# Power.net
KiCad netlist of a schematic drawn in Altium Designer
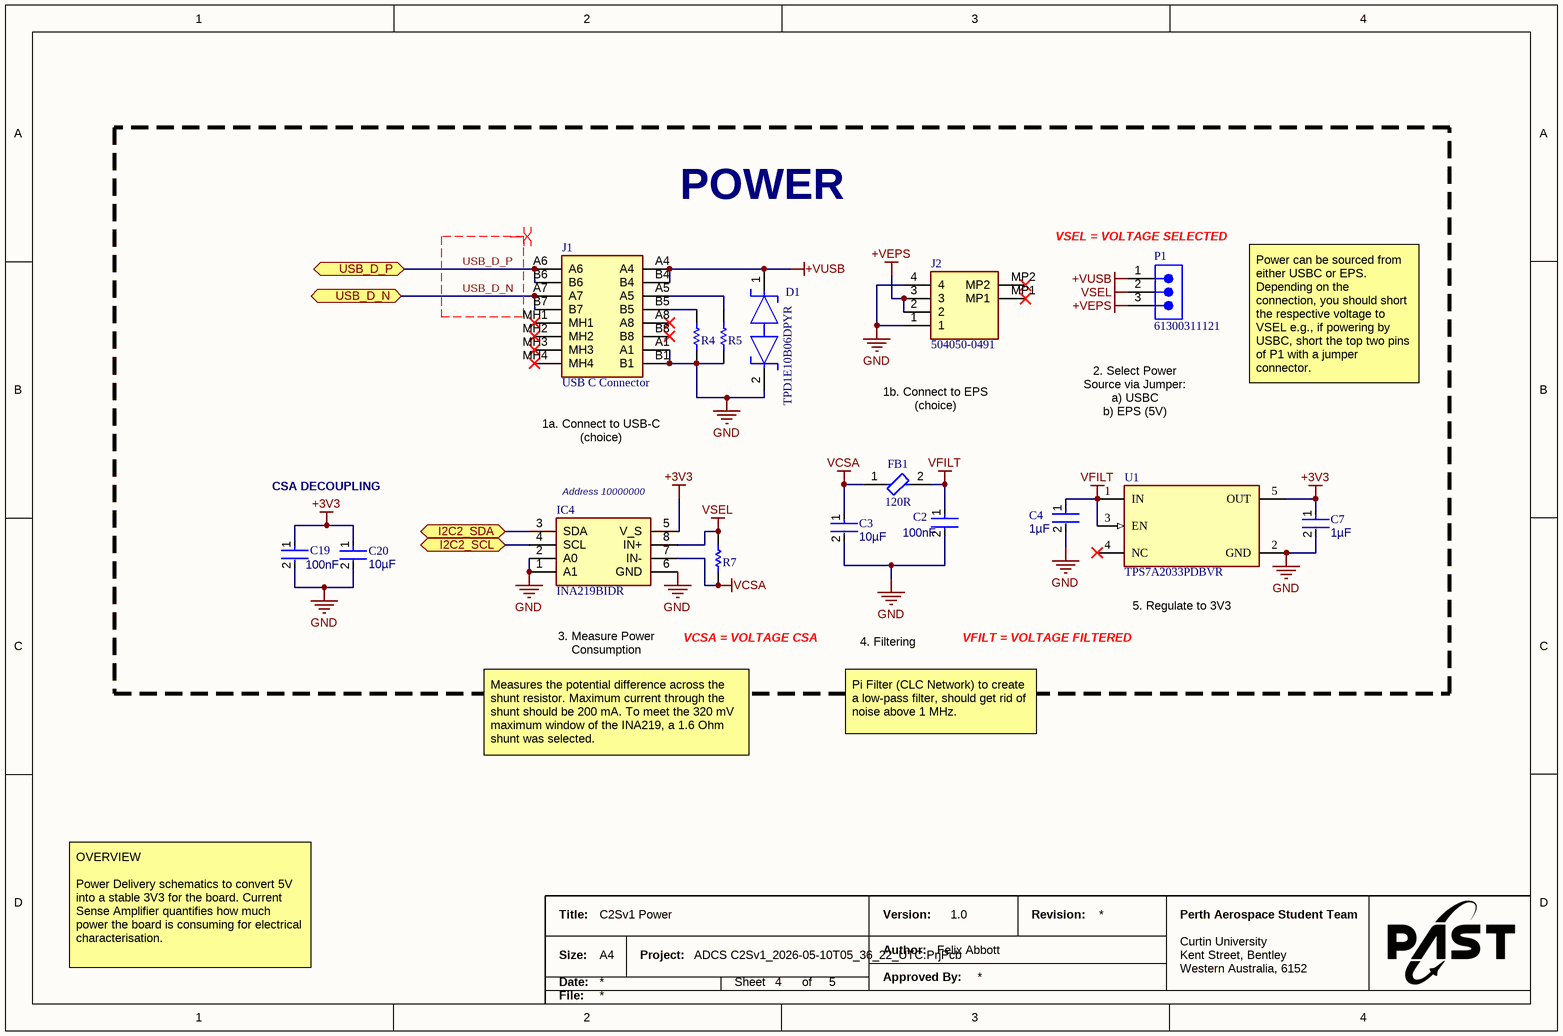
[diagram p0: Power.SchDoc]

(export (version "E")
  (design (tool "Eeschema 10.0.6"))
  (components
    (comp (ref "C2")
      (value "100nF")
      (footprint "FP-GCM188-0_1-IPC_B")
      (description "Cap Ceramic 0.1uF 50V X8L 20% Pad SMD 0603 150C Automotive T/R")
      (fields
        (field (name "TOLERANCE") "20%")
        (field (name "Comment") "GCM188L81H104MA57D")
        (field (name "ADDED BY") "Felix")
      )
      (libsource (lib "Perth Aerospace Student Team") (part "02cd4be3c70576c341d710602a673aa"))
    )
    (comp (ref "C3")
      (value "10µF")
      (footprint "FP-GCM188-0_2-IPC_B")
      (description "6.3V 10uF X7T ±20% 0603 Multilayer Ceramic Capacitors MLCC - SMD/SMT ROHS")
      (fields
        (field (name "TOLERANCE") "20%")
        (field (name "Comment") "GCM188D70J106ME36D")
        (field (name "ADDED BY") "Felix")
      )
      (libsource (lib "Perth Aerospace Student Team") (part "11868f565c42a9108669ba33697ecf6"))
    )
    (comp (ref "C4")
      (value "1µF")
      (footprint "FP-GCM188-0_1-IPC_B")
      (description "16V 1uF X7R ±10% 0603 Multilayer Ceramic Capacitors MLCC - SMD/SMT ROHS")
      (fields
        (field (name "TOLERANCE") "10%")
        (field (name "Comment") "GCM188R71C105KA64J")
        (field (name "ADDED BY") "Felix")
      )
      (libsource (lib "Perth Aerospace Student Team") (part "02cd4be3c70576c341d710602a673aa"))
    )
    (comp (ref "C7")
      (value "1µF")
      (footprint "FP-GCM188-0_1-IPC_B")
      (description "16V 1uF X7R ±10% 0603 Multilayer Ceramic Capacitors MLCC - SMD/SMT ROHS")
      (fields
        (field (name "TOLERANCE") "10%")
        (field (name "Comment") "GCM188R71C105KA64J")
        (field (name "ADDED BY") "Felix")
      )
      (libsource (lib "Perth Aerospace Student Team") (part "02cd4be3c70576c341d710602a673aa"))
    )
    (comp (ref "C19")
      (value "100nF")
      (footprint "FP-GCM188-0_1-IPC_B")
      (description "Cap Ceramic 0.1uF 50V X8L 20% Pad SMD 0603 150C Automotive T/R")
      (fields
        (field (name "TOLERANCE") "20%")
        (field (name "Comment") "GCM188L81H104MA57D")
        (field (name "ADDED BY") "Felix")
      )
      (libsource (lib "Perth Aerospace Student Team") (part "02cd4be3c70576c341d710602a673aa"))
    )
    (comp (ref "C20")
      (value "10µF")
      (footprint "FP-GCM188-0_2-IPC_B")
      (description "6.3V 10uF X7T ±20% 0603 Multilayer Ceramic Capacitors MLCC - SMD/SMT ROHS")
      (fields (field (name "TOLERANCE") "20%") (field (name "ADDED BY") "Felix"))
      (libsource (lib "Perth Aerospace Student Team") (part "11868f565c42a9108669ba33697ecf6"))
    )
    (comp (ref "D1")
      (value "TPD1E10B06DPYR")
      (footprint "FP-DPY0002A-MFG")
      (description "TVS DIODE 5.5V 14V 2X1SON")
      (libsource (lib "Altium Content Vault") (part "208e19b57522434895fa003e5d5b197"))
    )
    (comp (ref "FB1")
      (value "120R")
      (footprint "FP-BLM18-0_15-t0_6-d1_2-IPC_B")
      (description "Chip Ferrite Bead Array, 0603, 120Ω @ 100MHz, 25%, 0.03Ω, 3A")
      (libsource (lib "Altium Content Vault") (part "5f30dd21d616792df468990f7003faa"))
    )
    (comp (ref "IC4")
      (value "INA219BIDR")
      (footprint "SOIC127P600X175-8N")
      (description "Integrated Circuit")
      (fields (field (name "MOUSER PART NUMBER") "595-INA219BIDR") (field (name "AUTHOR") "Damon Stewart"))
      (libsource (lib "Perth Aerospace Student Team") (part "INA219BIDR"))
    )
    (comp (ref "J1")
      (value "USB C Connector")
      (footprint "UJ20CHGMSMT2P16TR")
      (description "UJ20-C-H-G-MSMT-2-P16-TR Connector")
      (fields
        (field (name "MOUSER PART NUMBER") "179-UJ20CHGMSMT2P16T")
        (field (name "MANUFACTURER_PART_NUMBER") "UJ20-C-H-G-MSMT-2-P16-TR")
        (field (name "AUTHOR") "Raphael Ho")
      )
      (libsource (lib "Perth Aerospace Student Team") (part "UJ20-C-H-G-MSMT-2-P16-TR"))
    )
    (comp (ref "J2")
      (value "504050-0491")
      (footprint "5040500491")
      (description "Connector")
      (fields (field (name "MOUSER PART NUMBER") "538-504050-0491"))
      (libsource (lib "Perth Aerospace Student Team") (part "504050-0491"))
    )
    (comp (ref "P1")
      (value "61300311121")
      (footprint "61300311121")
      (description "WR-PHD Pin Header, THT, Vertical, pitch 2.54mm, 1 Row, 3P")
      (fields (field (name "MANUFACTURER") "Wurth Elektronik"))
      (libsource (lib "Perth Aerospace Student Team") (part "62000311121"))
    )
    (comp (ref "R4")
      (value "5.1k")
      (footprint "RESC1608X55N")
      (description "AC0603FR-7W5K1L Resistor")
      (fields
        (field (name "MANUFACTURER_PART_NUMBER") "AC0603FR-7W5K1L")
        (field (name "AUTHOR") "Raphael Ho")
      )
      (libsource (lib "Perth Aerospace Student Team") (part "CRCW0603300RFKEAHP"))
    )
    (comp (ref "R5")
      (value "5.1k")
      (footprint "RESC1608X55N")
      (description "AC0603FR-7W5K1L Resistor")
      (fields
        (field (name "MANUFACTURER_PART_NUMBER") "AC0603FR-7W5K1L")
        (field (name "AUTHOR") "Raphael Ho")
      )
      (libsource (lib "Perth Aerospace Student Team") (part "CRCW0603300RFKEAHP"))
    )
    (comp (ref "R7")
      (value "ERJ-6DQF1R6V")
      (footprint "ERJ6_B_BW_R_LW_CW_D")
      (description "SMD Current Sense Resistor")
      (fields (field (name "MOUSER PART NUMBER") "667-ERJ-6DQF1R6V") (field (name "ADDED BY") "Felix"))
      (libsource (lib "Perth Aerospace Student Team") (part "ERJ-6DQF1R6V"))
    )
    (comp (ref "U1")
      (value "TPS7A2033PDBVR")
      (footprint "FP-DBV0005A-IPC_B")
      (description "300mA ultra-low-noise low-IQ low-dropout (LDO) linear regulator with high PSRR 5-SOT-23 -40 to 125")
      (fields (field (name "ADDED BY") "Felix Abbott"))
      (libsource (lib "Perth Aerospace Student Team") (part "76aa7ad0ceb1012e0d85aeafc53095f"))
    )
  )
  (nets
    (net (code "1") (name "+3V3") (class "Default")
      (node (ref "C19") (pin "1") (pinfunction "1_1") (pintype "passive"))
      (node (ref "C20") (pin "1") (pinfunction "1_1") (pintype "passive"))
      (node (ref "C7") (pin "1") (pinfunction "1_1") (pintype "passive"))
      (node (ref "IC4") (pin "5") (pinfunction "V_S_5") (pintype "passive"))
      (node (ref "U1") (pin "5") (pinfunction "OUT_5") (pintype "passive"))
    )
    (net (code "2") (name "+VEPS") (class "Default")
      (node (ref "J2") (pin "2") (pinfunction "2_2") (pintype "passive"))
      (node (ref "J2") (pin "3") (pinfunction "3_3") (pintype "passive"))
      (node (ref "P1") (pin "3") (pinfunction "3_3") (pintype "passive"))
    )
    (net (code "3") (name "+VUSB") (class "Default")
      (node (ref "D1") (pin "1") (pinfunction "1_1") (pintype "passive"))
      (node (ref "J1") (pin "A4") (pinfunction "A4_A4") (pintype "passive"))
      (node (ref "J1") (pin "B4") (pinfunction "B4_B4") (pintype "passive"))
      (node (ref "P1") (pin "1") (pinfunction "1_1") (pintype "passive"))
    )
    (net (code "4") (name "/I2C2_SCL") (class "Default")
      (node (ref "IC4") (pin "4") (pinfunction "SCL_4") (pintype "passive"))
    )
    (net (code "5") (name "/I2C2_SDA") (class "Default")
      (node (ref "IC4") (pin "3") (pinfunction "SDA_3") (pintype "passive"))
    )
    (net (code "6") (name "/USB_D_N") (class "Default")
      (node (ref "J1") (pin "A7") (pinfunction "A7_A7") (pintype "passive"))
      (node (ref "J1") (pin "B7") (pinfunction "B7_B7") (pintype "passive"))
    )
    (net (code "7") (name "/USB_D_P") (class "Default")
      (node (ref "J1") (pin "A6") (pinfunction "A6_A6") (pintype "passive"))
      (node (ref "J1") (pin "B6") (pinfunction "B6_B6") (pintype "passive"))
    )
    (net (code "8") (name "GND") (class "Default")
      (node (ref "C19") (pin "2") (pinfunction "2_2") (pintype "passive"))
      (node (ref "C2") (pin "2") (pinfunction "2_2") (pintype "passive"))
      (node (ref "C20") (pin "2") (pinfunction "2_2") (pintype "passive"))
      (node (ref "C3") (pin "2") (pinfunction "2_2") (pintype "passive"))
      (node (ref "C4") (pin "2") (pinfunction "2_2") (pintype "passive"))
      (node (ref "C7") (pin "2") (pinfunction "2_2") (pintype "passive"))
      (node (ref "D1") (pin "2") (pinfunction "2_2") (pintype "passive"))
      (node (ref "IC4") (pin "1") (pinfunction "A1_1") (pintype "passive"))
      (node (ref "IC4") (pin "2") (pinfunction "A0_2") (pintype "passive"))
      (node (ref "IC4") (pin "6") (pinfunction "GND_6") (pintype "passive"))
      (node (ref "J1") (pin "A1") (pinfunction "A1_A1") (pintype "passive"))
      (node (ref "J1") (pin "B1") (pinfunction "B1_B1") (pintype "passive"))
      (node (ref "J2") (pin "1") (pinfunction "1_1") (pintype "passive"))
      (node (ref "J2") (pin "4") (pinfunction "4_4") (pintype "passive"))
      (node (ref "R4") (pin "2") (pinfunction "2_2") (pintype "passive"))
      (node (ref "R5") (pin "2") (pinfunction "2_2") (pintype "passive"))
      (node (ref "U1") (pin "2") (pinfunction "GND_2") (pintype "power_in"))
    )
    (net (code "9") (name "Net-(J1-PadA5)") (class "Default")
      (node (ref "J1") (pin "A5") (pinfunction "A5_A5") (pintype "passive"))
      (node (ref "R5") (pin "1") (pinfunction "1_1") (pintype "passive"))
    )
    (net (code "10") (name "Net-(J1-PadB5)") (class "Default")
      (node (ref "J1") (pin "B5") (pinfunction "B5_B5") (pintype "passive"))
      (node (ref "R4") (pin "1") (pinfunction "1_1") (pintype "passive"))
    )
    (net (code "11") (name "VCSA") (class "Default")
      (node (ref "C3") (pin "1") (pinfunction "1_1") (pintype "passive"))
      (node (ref "FB1") (pin "1") (pinfunction "1_1") (pintype "passive"))
      (node (ref "IC4") (pin "7") (pinfunction "IN-_7") (pintype "passive"))
      (node (ref "R7") (pin "1") (pinfunction "1_1") (pintype "passive"))
    )
    (net (code "12") (name "VFILT") (class "Default")
      (node (ref "C2") (pin "1") (pinfunction "1_1") (pintype "passive"))
      (node (ref "C4") (pin "1") (pinfunction "1_1") (pintype "passive"))
      (node (ref "FB1") (pin "2") (pinfunction "2_2") (pintype "passive"))
      (node (ref "U1") (pin "1") (pinfunction "IN_1") (pintype "power_in"))
      (node (ref "U1") (pin "3") (pinfunction "EN_3") (pintype "input"))
    )
    (net (code "13") (name "VSEL") (class "Default")
      (node (ref "IC4") (pin "8") (pinfunction "IN+_8") (pintype "passive"))
      (node (ref "P1") (pin "2") (pinfunction "2_2") (pintype "passive"))
      (node (ref "R7") (pin "2") (pinfunction "2_2") (pintype "passive"))
    )
    (net (code "14") (name "unconnected-(J1-PadA8)") (class "Default")
      (node (ref "J1") (pin "A8") (pinfunction "A8_A8") (pintype "passive+no_connect"))
    )
    (net (code "15") (name "unconnected-(J1-PadB8)") (class "Default")
      (node (ref "J1") (pin "B8") (pinfunction "B8_B8") (pintype "passive+no_connect"))
    )
    (net (code "16") (name "unconnected-(J1-PadMH1)") (class "Default")
      (node (ref "J1") (pin "MH1") (pinfunction "MH1_MH1") (pintype "passive+no_connect"))
    )
    (net (code "17") (name "unconnected-(J1-PadMH2)") (class "Default")
      (node (ref "J1") (pin "MH2") (pinfunction "MH2_MH2") (pintype "passive+no_connect"))
    )
    (net (code "18") (name "unconnected-(J1-PadMH3)") (class "Default")
      (node (ref "J1") (pin "MH3") (pinfunction "MH3_MH3") (pintype "passive+no_connect"))
    )
    (net (code "19") (name "unconnected-(J1-PadMH4)") (class "Default")
      (node (ref "J1") (pin "MH4") (pinfunction "MH4_MH4") (pintype "passive+no_connect"))
    )
    (net (code "20") (name "unconnected-(J2-PadMP1)") (class "Default")
      (node (ref "J2") (pin "MP1") (pinfunction "MP1_MP1") (pintype "passive+no_connect"))
    )
    (net (code "21") (name "unconnected-(J2-PadMP2)") (class "Default")
      (node (ref "J2") (pin "MP2") (pinfunction "MP2_MP2") (pintype "passive+no_connect"))
    )
    (net (code "22") (name "unconnected-(U1-NC-Pad4)") (class "Default")
      (node (ref "U1") (pin "4") (pinfunction "NC_4") (pintype "passive+no_connect"))
    )
  )
)
